# ucus_kontrol.net
KiCad netlist of a schematic drawn in Altium Designer
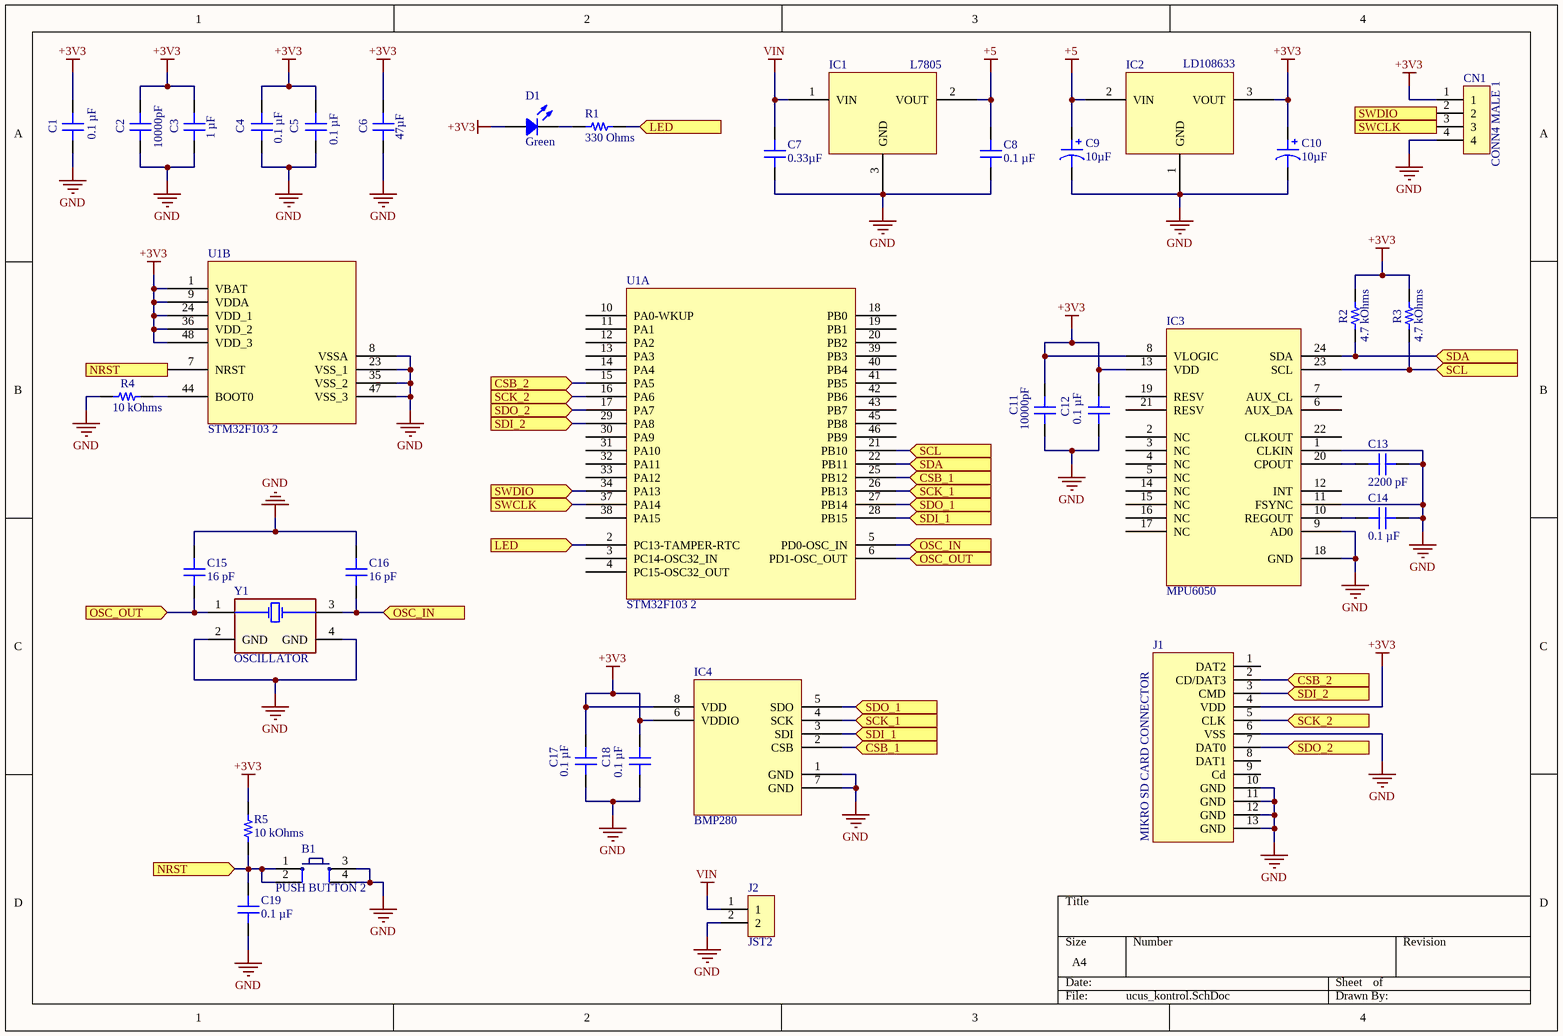
[diagram p0: ucus_kontrol.SchDoc]

(export (version "E")
  (design (tool "Eeschema 10.0.6"))
  (components
    (comp (ref "B1")
      (value "PUSH BUTTON 2")
      (footprint "PUSH BUTTON 2")
      (libsource (lib "UcusKontrol_Library") (part "PUSH BUTTON 2"))
    )
    (comp (ref "C1")
      (value "0.1 µF")
      (footprint "CAP 1206_3216 - 0.8MM")
      (description "CAP CER 0.1UF 50V X7R 1206")
      (fields
        (field (name "PART NUMBER") "1206B104M500CT")
        (field (name "MANUFACTURER") "Walsin Technology Corporation")
      )
      (libsource (lib "Celestial Altium Library - altium_library") (part "Capacitor"))
    )
    (comp (ref "C2")
      (value "10000pF")
      (footprint "CAP 1206_3216 - 1.0MM")
      (description "CAP CER 10000PF 50V X7R 1206")
      (fields (field (name "PART NUMBER") "12065C103K4T2A") (field (name "MANUFACTURER") "AVX Corporation"))
      (libsource (lib "Celestial Altium Library - altium_library") (part "Capacitor"))
    )
    (comp (ref "C3")
      (value "1 µF")
      (footprint "CAP 1206_3216 - 0.8MM")
      (description "CAP CER 1206 1UF 25V X7R")
      (fields (field (name "PART NUMBER") "C1206X105K3RAC3316") (field (name "MANUFACTURER") "KEMET"))
      (libsource (lib "Celestial Altium Library - altium_library") (part "Capacitor"))
    )
    (comp (ref "C4")
      (value "0.1 µF")
      (footprint "CAP 1206_3216 - 0.8MM")
      (description "CAP CER 0.1UF 50V X7R 1206")
      (fields
        (field (name "PART NUMBER") "1206B104M500CT")
        (field (name "MANUFACTURER") "Walsin Technology Corporation")
      )
      (libsource (lib "Celestial Altium Library - altium_library") (part "Capacitor"))
    )
    (comp (ref "C5")
      (value "0.1 µF")
      (footprint "CAP 1206_3216 - 0.8MM")
      (description "CAP CER 0.1UF 50V X7R 1206")
      (fields
        (field (name "PART NUMBER") "1206B104M500CT")
        (field (name "MANUFACTURER") "Walsin Technology Corporation")
      )
      (libsource (lib "Celestial Altium Library - altium_library") (part "Capacitor"))
    )
    (comp (ref "C6")
      (value "47µF")
      (footprint "CAP 1206_3216 - 1.8MM")
      (description "CAP CER 47UF 6.3V X5R 1206")
      (fields (field (name "PART NUMBER") "12066D476MAT2A") (field (name "MANUFACTURER") "AVX Corporation"))
      (libsource (lib "Celestial Altium Library - altium_library") (part "Capacitor"))
    )
    (comp (ref "C7")
      (value "0.33µF")
      (footprint "CAP 1206_3216 - 1.0MM")
      (description "CAP CER 0.33UF 50V Z5U 1206")
      (fields (field (name "PART NUMBER") "12065E334MAT2A") (field (name "MANUFACTURER") "AVX Corporation"))
      (libsource (lib "Celestial Altium Library - altium_library") (part "Capacitor"))
    )
    (comp (ref "C8")
      (value "0.1 µF")
      (footprint "CAP 1206_3216 - 0.8MM")
      (description "CAP CER 0.1UF 50V X7R 1206")
      (fields
        (field (name "PART NUMBER") "1206B104M500CT")
        (field (name "MANUFACTURER") "Walsin Technology Corporation")
      )
      (libsource (lib "Celestial Altium Library - altium_library") (part "Capacitor"))
    )
    (comp (ref "C9")
      (value "10µF")
      (footprint "CAP POL 1206_3216")
      (description "CAP TANT 10UF 20% 25V 1206")
      (fields (field (name "PART NUMBER") "F951E106MAAAQ2") (field (name "MANUFACTURER") "AVX Corporation"))
      (libsource (lib "Celestial Altium Library - altium_library") (part "Polarised Capacitor"))
    )
    (comp (ref "C10")
      (value "10µF")
      (footprint "CAP POL 1206_3216")
      (description "CAP TANT 10UF 20% 25V 1206")
      (fields (field (name "PART NUMBER") "F951E106MAAAQ2") (field (name "MANUFACTURER") "AVX Corporation"))
      (libsource (lib "Celestial Altium Library - altium_library") (part "Polarised Capacitor"))
    )
    (comp (ref "C11")
      (value "10000pF")
      (footprint "CAP 1206_3216 - 1.0MM")
      (description "CAP CER 10000PF 50V X7R 1206")
      (fields (field (name "PART NUMBER") "12065C103K4T2A") (field (name "MANUFACTURER") "AVX Corporation"))
      (libsource (lib "Celestial Altium Library - altium_library") (part "Capacitor"))
    )
    (comp (ref "C12")
      (value "0.1 µF")
      (footprint "CAP 1206_3216 - 0.8MM")
      (description "CAP CER 0.1UF 50V X7R 1206")
      (fields
        (field (name "PART NUMBER") "1206B104M500CT")
        (field (name "MANUFACTURER") "Walsin Technology Corporation")
      )
      (libsource (lib "Celestial Altium Library - altium_library") (part "Capacitor"))
    )
    (comp (ref "C13")
      (value "2200 pF")
      (footprint "CAP 1206_3216 - 0.8MM")
      (description "CAP CER 2200PF 50V C0G/NP0 1206")
      (fields
        (field (name "PART NUMBER") "CL31C222JBCNNNC")
        (field (name "MANUFACTURER") "Samsung Electro-Mechanics")
      )
      (libsource (lib "Celestial Altium Library - altium_library") (part "Capacitor"))
    )
    (comp (ref "C14")
      (value "0.1 µF")
      (footprint "CAP 1206_3216 - 0.8MM")
      (description "CAP CER 0.1UF 50V X7R 1206")
      (fields
        (field (name "PART NUMBER") "1206B104M500CT")
        (field (name "MANUFACTURER") "Walsin Technology Corporation")
      )
      (libsource (lib "Celestial Altium Library - altium_library") (part "Capacitor"))
    )
    (comp (ref "C15")
      (value "16 pF")
      (footprint "CAP 1206_3216 - 0.8MM")
      (description "CAP CER 16PF 50V NP0 1206")
      (fields (field (name "PART NUMBER") "C1206C160J5GAC7800") (field (name "MANUFACTURER") "KEMET"))
      (libsource (lib "Celestial Altium Library - altium_library") (part "Capacitor"))
    )
    (comp (ref "C16")
      (value "16 pF")
      (footprint "CAP 1206_3216 - 0.8MM")
      (description "CAP CER 16PF 50V NP0 1206")
      (fields (field (name "PART NUMBER") "C1206C160J5GAC7800") (field (name "MANUFACTURER") "KEMET"))
      (libsource (lib "Celestial Altium Library - altium_library") (part "Capacitor"))
    )
    (comp (ref "C17")
      (value "0.1 µF")
      (footprint "CAP 1206_3216 - 0.8MM")
      (description "CAP CER 0.1UF 50V X7R 1206")
      (fields
        (field (name "PART NUMBER") "1206B104M500CT")
        (field (name "MANUFACTURER") "Walsin Technology Corporation")
      )
      (libsource (lib "Celestial Altium Library - altium_library") (part "Capacitor"))
    )
    (comp (ref "C18")
      (value "0.1 µF")
      (footprint "CAP 1206_3216 - 0.8MM")
      (description "CAP CER 0.1UF 50V X7R 1206")
      (fields
        (field (name "PART NUMBER") "1206B104M500CT")
        (field (name "MANUFACTURER") "Walsin Technology Corporation")
      )
      (libsource (lib "Celestial Altium Library - altium_library") (part "Capacitor"))
    )
    (comp (ref "C19")
      (value "0.1 µF")
      (footprint "CAP 1206_3216 - 0.8MM")
      (description "CAP CER 0.1UF 50V X7R 1206")
      (fields
        (field (name "PART NUMBER") "1206B104M500CT")
        (field (name "MANUFACTURER") "Walsin Technology Corporation")
      )
      (libsource (lib "Celestial Altium Library - altium_library") (part "Capacitor"))
    )
    (comp (ref "CN1")
      (value "CONN4 MALE 1")
      (footprint "CONN4 MALE 1")
      (description "4 PIN 2.54MM")
      (libsource (lib "UcusKontrol_Library") (part "CONN4 MALE 1"))
    )
    (comp (ref "D1")
      (value "Green")
      (footprint "LED 0805_2012 GREEN")
      (description "LED GREEN 0805 SMD")
      (fields (field (name "PART NUMBER") "5975316507F") (field (name "MANUFACTURER") "Dialight"))
      (libsource (lib "Celestial Altium Library - altium_library") (part "LED"))
    )
    (comp (ref "IC1")
      (value "L7805")
      (footprint "DPAK")
      (description "IC-7805 V.REG.+5V 1.5A DPAK TO252")
      (libsource (lib "UcusKontrol_Library") (part "L7805"))
    )
    (comp (ref "IC2")
      (value "LD108633")
      (footprint "DPAK")
      (description "IC-1086 V.REG LDO 3.3V 1.5A TO-252 (DPAK)")
      (libsource (lib "UcusKontrol_Library") (part "LD108633"))
    )
    (comp (ref "IC3")
      (value "MPU6050")
      (footprint "QFN")
      (description "IC-6050 SENSOR MOTION QFN24")
      (libsource (lib "UcusKontrol_Library") (part "MPU6050"))
    )
    (comp (ref "IC4")
      (value "BMP280")
      (footprint "BMP280")
      (libsource (lib "UcusKontrol_Library") (part "BMP280"))
    )
    (comp (ref "J1")
      (value "MIKRO SD CARD CONNECTOR")
      (footprint "MICRO SD CARD CONNECTOR")
      (libsource (lib "UcusKontrol_Library") (part "MIKRO SD CARD CONNECTOR"))
    )
    (comp (ref "J2")
      (value "JST2")
      (footprint "JST2")
      (description "2 PIN 2.54MM")
      (libsource (lib "UcusKontrol_Library") (part "JST2"))
    )
    (comp (ref "R1")
      (value "330 Ohms")
      (footprint "RES 0805_2012")
      (description "RES SMD 330 OHM 1% 1/8W 0805")
      (fields (field (name "PART NUMBER") "AC0805FR-07330RL") (field (name "MANUFACTURER") "Yageo"))
      (libsource (lib "Celestial Altium Library - altium_library") (part "Resistor"))
    )
    (comp (ref "R2")
      (value "4.7 kOhms")
      (footprint "RES 1206_3216")
      (description "RES 4.7K OHM 0.1% 2/5W 1206")
      (fields (field (name "PART NUMBER") "TNPW12064K70BEEA") (field (name "MANUFACTURER") "Vishay Dale"))
      (libsource (lib "Celestial Altium Library - altium_library") (part "Resistor"))
    )
    (comp (ref "R3")
      (value "4.7 kOhms")
      (footprint "RES 1206_3216")
      (description "RES 4.7K OHM 0.1% 2/5W 1206")
      (fields (field (name "PART NUMBER") "TNPW12064K70BEEA") (field (name "MANUFACTURER") "Vishay Dale"))
      (libsource (lib "Celestial Altium Library - altium_library") (part "Resistor"))
    )
    (comp (ref "R4")
      (value "10 kOhms")
      (footprint "RES 1206_3216")
      (description "RES SMD 10K OHM 1% 1/4W 1206")
      (fields (field (name "PART NUMBER") "CRCW120610K0FKTA") (field (name "MANUFACTURER") "Vishay Dale"))
      (libsource (lib "Celestial Altium Library - altium_library") (part "Resistor"))
    )
    (comp (ref "R5")
      (value "10 kOhms")
      (footprint "RES 1206_3216")
      (description "RES SMD 10K OHM 1% 1/4W 1206")
      (fields (field (name "PART NUMBER") "CRCW120610K0FKTA") (field (name "MANUFACTURER") "Vishay Dale"))
      (libsource (lib "Celestial Altium Library - altium_library") (part "Resistor"))
    )
    (comp (ref "U1")
      (value "STM32F103 2")
      (footprint "LQFP48")
      (libsource (lib "UcusKontrol_Library") (part "STM32F103 2"))
    )
    (comp (ref "Y1")
      (value "OSCILLATOR")
      (footprint "OSCILLATOR")
      (description "8MHZ 12.5pF")
      (libsource (lib "UcusKontrol_Library") (part "OSCILLATOR"))
    )
  )
  (nets
    (net (code "1") (name "+3V3") (class "Default")
      (node (ref "C1") (pin "2") (pinfunction "2_2") (pintype "passive"))
      (node (ref "C10") (pin "1") (pinfunction "1_1") (pintype "passive"))
      (node (ref "C11") (pin "2") (pinfunction "2_2") (pintype "passive"))
      (node (ref "C12") (pin "1") (pinfunction "1_1") (pintype "passive"))
      (node (ref "C17") (pin "2") (pinfunction "2_2") (pintype "passive"))
      (node (ref "C18") (pin "2") (pinfunction "2_2") (pintype "passive"))
      (node (ref "C2") (pin "2") (pinfunction "2_2") (pintype "passive"))
      (node (ref "C3") (pin "2") (pinfunction "2_2") (pintype "passive"))
      (node (ref "C4") (pin "2") (pinfunction "2_2") (pintype "passive"))
      (node (ref "C5") (pin "2") (pinfunction "2_2") (pintype "passive"))
      (node (ref "C6") (pin "2") (pinfunction "2_2") (pintype "passive"))
      (node (ref "CN1") (pin "1") (pinfunction "1_1") (pintype "passive"))
      (node (ref "D1") (pin "1") (pinfunction "1_1") (pintype "passive"))
      (node (ref "IC2") (pin "3") (pinfunction "VOUT_3") (pintype "passive"))
      (node (ref "IC3") (pin "13") (pinfunction "VDD_13") (pintype "passive"))
      (node (ref "IC3") (pin "8") (pinfunction "VLOGIC_8") (pintype "passive"))
      (node (ref "IC4") (pin "6") (pinfunction "VDDIO_6") (pintype "passive"))
      (node (ref "IC4") (pin "8") (pinfunction "VDD_8") (pintype "passive"))
      (node (ref "J1") (pin "4") (pinfunction "VDD_4") (pintype "passive"))
      (node (ref "R2") (pin "2") (pinfunction "2_2") (pintype "passive"))
      (node (ref "R3") (pin "2") (pinfunction "2_2") (pintype "passive"))
      (node (ref "R5") (pin "2") (pinfunction "2_2") (pintype "passive"))
      (node (ref "U1") (pin "1") (pinfunction "VBAT_1") (pintype "passive"))
      (node (ref "U1") (pin "24") (pinfunction "VDD_1_24") (pintype "passive"))
      (node (ref "U1") (pin "36") (pinfunction "VDD_2_36") (pintype "passive"))
      (node (ref "U1") (pin "48") (pinfunction "VDD_3_48") (pintype "passive"))
      (node (ref "U1") (pin "9") (pinfunction "VDDA_9") (pintype "passive"))
    )
    (net (code "2") (name "+5") (class "Default")
      (node (ref "C8") (pin "2") (pinfunction "2_2") (pintype "passive"))
      (node (ref "C9") (pin "1") (pinfunction "1_1") (pintype "passive"))
      (node (ref "IC1") (pin "2") (pinfunction "VOUT_2") (pintype "passive"))
      (node (ref "IC2") (pin "2") (pinfunction "VIN_2") (pintype "passive"))
    )
    (net (code "3") (name "/CSB_1") (class "Default")
      (node (ref "IC4") (pin "2") (pinfunction "CSB_2") (pintype "passive"))
      (node (ref "U1") (pin "25") (pinfunction "PB12_25") (pintype "passive"))
    )
    (net (code "4") (name "/CSB_2") (class "Default")
      (node (ref "J1") (pin "2") (pinfunction "CD/DAT3_2") (pintype "passive"))
      (node (ref "U1") (pin "15") (pinfunction "PA5_15") (pintype "passive"))
    )
    (net (code "5") (name "/LED") (class "Default")
      (node (ref "R1") (pin "2") (pinfunction "2_2") (pintype "passive"))
      (node (ref "U1") (pin "2") (pinfunction "PC13-TAMPER-RTC_2") (pintype "passive"))
    )
    (net (code "6") (name "/NRST") (class "Default")
      (node (ref "B1") (pin "1") (pinfunction "1_1") (pintype "passive"))
      (node (ref "B1") (pin "2") (pinfunction "2_2") (pintype "passive"))
      (node (ref "C19") (pin "2") (pinfunction "2_2") (pintype "passive"))
      (node (ref "R5") (pin "1") (pinfunction "1_1") (pintype "passive"))
      (node (ref "U1") (pin "7") (pinfunction "NRST_7") (pintype "passive"))
    )
    (net (code "7") (name "/OSC_IN") (class "Default")
      (node (ref "C16") (pin "1") (pinfunction "1_1") (pintype "passive"))
      (node (ref "U1") (pin "5") (pinfunction "PD0-OSC_IN_5") (pintype "passive"))
      (node (ref "Y1") (pin "3") (pintype "passive"))
    )
    (net (code "8") (name "/OSC_OUT") (class "Default")
      (node (ref "C15") (pin "1") (pinfunction "1_1") (pintype "passive"))
      (node (ref "U1") (pin "6") (pinfunction "PD1-OSC_OUT_6") (pintype "passive"))
      (node (ref "Y1") (pin "1") (pintype "power_in"))
    )
    (net (code "9") (name "/SCK_1") (class "Default")
      (node (ref "IC4") (pin "4") (pinfunction "SCK_4") (pintype "passive"))
      (node (ref "U1") (pin "26") (pinfunction "PB13_26") (pintype "passive"))
    )
    (net (code "10") (name "/SCK_2") (class "Default")
      (node (ref "J1") (pin "5") (pinfunction "CLK_5") (pintype "passive"))
      (node (ref "U1") (pin "16") (pinfunction "PA6_16") (pintype "passive"))
    )
    (net (code "11") (name "/SCL") (class "Default")
      (node (ref "IC3") (pin "23") (pinfunction "SCL_23") (pintype "passive"))
      (node (ref "R3") (pin "1") (pinfunction "1_1") (pintype "passive"))
      (node (ref "U1") (pin "21") (pinfunction "PB10_21") (pintype "passive"))
    )
    (net (code "12") (name "/SDA") (class "Default")
      (node (ref "IC3") (pin "24") (pinfunction "SDA_24") (pintype "passive"))
      (node (ref "R2") (pin "1") (pinfunction "1_1") (pintype "passive"))
      (node (ref "U1") (pin "22") (pinfunction "PB11_22") (pintype "passive"))
    )
    (net (code "13") (name "/SDI_1") (class "Default")
      (node (ref "IC4") (pin "3") (pinfunction "SDI_3") (pintype "passive"))
      (node (ref "U1") (pin "28") (pinfunction "PB15_28") (pintype "passive"))
    )
    (net (code "14") (name "/SDI_2") (class "Default")
      (node (ref "J1") (pin "3") (pinfunction "CMD_3") (pintype "passive"))
      (node (ref "U1") (pin "29") (pinfunction "PA8_29") (pintype "passive"))
    )
    (net (code "15") (name "/SDO_1") (class "Default")
      (node (ref "IC4") (pin "5") (pinfunction "SDO_5") (pintype "passive"))
      (node (ref "U1") (pin "27") (pinfunction "PB14_27") (pintype "passive"))
    )
    (net (code "16") (name "/SDO_2") (class "Default")
      (node (ref "J1") (pin "7") (pinfunction "DAT0_7") (pintype "passive"))
      (node (ref "U1") (pin "17") (pinfunction "PA7_17") (pintype "passive"))
    )
    (net (code "17") (name "/SWCLK") (class "Default")
      (node (ref "CN1") (pin "3") (pinfunction "3_3") (pintype "passive"))
      (node (ref "U1") (pin "37") (pinfunction "PA14_37") (pintype "passive"))
    )
    (net (code "18") (name "/SWDIO") (class "Default")
      (node (ref "CN1") (pin "2") (pinfunction "2_2") (pintype "passive"))
      (node (ref "U1") (pin "34") (pinfunction "PA13_34") (pintype "passive"))
    )
    (net (code "19") (name "GND") (class "Default")
      (node (ref "B1") (pin "3") (pinfunction "3_3") (pintype "passive"))
      (node (ref "B1") (pin "4") (pinfunction "4_4") (pintype "passive"))
      (node (ref "C1") (pin "1") (pinfunction "1_1") (pintype "passive"))
      (node (ref "C10") (pin "2") (pinfunction "2_2") (pintype "passive"))
      (node (ref "C11") (pin "1") (pinfunction "1_1") (pintype "passive"))
      (node (ref "C12") (pin "2") (pinfunction "2_2") (pintype "passive"))
      (node (ref "C13") (pin "2") (pinfunction "2_2") (pintype "passive"))
      (node (ref "C14") (pin "2") (pinfunction "2_2") (pintype "passive"))
      (node (ref "C15") (pin "2") (pinfunction "2_2") (pintype "passive"))
      (node (ref "C16") (pin "2") (pinfunction "2_2") (pintype "passive"))
      (node (ref "C17") (pin "1") (pinfunction "1_1") (pintype "passive"))
      (node (ref "C18") (pin "1") (pinfunction "1_1") (pintype "passive"))
      (node (ref "C19") (pin "1") (pinfunction "1_1") (pintype "passive"))
      (node (ref "C2") (pin "1") (pinfunction "1_1") (pintype "passive"))
      (node (ref "C3") (pin "1") (pinfunction "1_1") (pintype "passive"))
      (node (ref "C4") (pin "1") (pinfunction "1_1") (pintype "passive"))
      (node (ref "C5") (pin "1") (pinfunction "1_1") (pintype "passive"))
      (node (ref "C6") (pin "1") (pinfunction "1_1") (pintype "passive"))
      (node (ref "C7") (pin "1") (pinfunction "1_1") (pintype "passive"))
      (node (ref "C8") (pin "1") (pinfunction "1_1") (pintype "passive"))
      (node (ref "C9") (pin "2") (pinfunction "2_2") (pintype "passive"))
      (node (ref "CN1") (pin "4") (pinfunction "4_4") (pintype "passive"))
      (node (ref "IC1") (pin "3") (pinfunction "GND_3") (pintype "passive"))
      (node (ref "IC2") (pin "1") (pinfunction "GND_1") (pintype "passive"))
      (node (ref "IC3") (pin "1") (pinfunction "CLKIN_1") (pintype "passive"))
      (node (ref "IC3") (pin "11") (pinfunction "FSYNC_11") (pintype "passive"))
      (node (ref "IC3") (pin "18") (pinfunction "GND_18") (pintype "passive"))
      (node (ref "IC3") (pin "9") (pinfunction "AD0_9") (pintype "passive"))
      (node (ref "IC4") (pin "1") (pinfunction "GND_1") (pintype "passive"))
      (node (ref "IC4") (pin "7") (pinfunction "GND_7") (pintype "passive"))
      (node (ref "J1") (pin "10") (pinfunction "GND_10") (pintype "passive"))
      (node (ref "J1") (pin "11") (pinfunction "GND_11") (pintype "passive"))
      (node (ref "J1") (pin "12") (pinfunction "GND_12") (pintype "passive"))
      (node (ref "J1") (pin "13") (pinfunction "GND_13") (pintype "passive"))
      (node (ref "J1") (pin "6") (pinfunction "VSS_6") (pintype "passive"))
      (node (ref "J2") (pin "2") (pinfunction "2_2") (pintype "passive"))
      (node (ref "R4") (pin "1") (pinfunction "1_1") (pintype "passive"))
      (node (ref "U1") (pin "23") (pinfunction "VSS_1_23") (pintype "passive"))
      (node (ref "U1") (pin "35") (pinfunction "VSS_2_35") (pintype "passive"))
      (node (ref "U1") (pin "47") (pinfunction "VSS_3_47") (pintype "passive"))
      (node (ref "U1") (pin "8") (pinfunction "VSSA_8") (pintype "passive"))
      (node (ref "Y1") (pin "2") (pinfunction "GND_2") (pintype "power_in"))
      (node (ref "Y1") (pin "4") (pinfunction "GND_4") (pintype "passive"))
    )
    (net (code "20") (name "Net-(D1-Pad2)") (class "Default")
      (node (ref "D1") (pin "2") (pinfunction "2_2") (pintype "passive"))
      (node (ref "R1") (pin "1") (pinfunction "1_1") (pintype "passive"))
    )
    (net (code "21") (name "Net-(IC3-CPOUT)") (class "Default")
      (node (ref "C13") (pin "1") (pinfunction "1_1") (pintype "passive"))
      (node (ref "IC3") (pin "20") (pinfunction "CPOUT_20") (pintype "passive"))
    )
    (net (code "22") (name "Net-(IC3-REGOUT)") (class "Default")
      (node (ref "C14") (pin "1") (pinfunction "1_1") (pintype "passive"))
      (node (ref "IC3") (pin "10") (pinfunction "REGOUT_10") (pintype "passive"))
    )
    (net (code "23") (name "Net-(U1B-BOOT0)") (class "Default")
      (node (ref "R4") (pin "2") (pinfunction "2_2") (pintype "passive"))
      (node (ref "U1") (pin "44") (pinfunction "BOOT0_44") (pintype "passive"))
    )
    (net (code "24") (name "VIN") (class "Default")
      (node (ref "C7") (pin "2") (pinfunction "2_2") (pintype "passive"))
      (node (ref "IC1") (pin "1") (pinfunction "VIN_1") (pintype "passive"))
      (node (ref "J2") (pin "1") (pinfunction "1_1") (pintype "passive"))
    )
    (net (code "25") (name "unconnected-(IC3-AUX_CL-Pad7)") (class "Default")
      (node (ref "IC3") (pin "7") (pinfunction "AUX_CL_7") (pintype "passive"))
    )
    (net (code "26") (name "unconnected-(IC3-AUX_DA-Pad6)") (class "Default")
      (node (ref "IC3") (pin "6") (pinfunction "AUX_DA_6") (pintype "passive"))
    )
    (net (code "27") (name "unconnected-(IC3-CLKOUT-Pad22)") (class "Default")
      (node (ref "IC3") (pin "22") (pinfunction "CLKOUT_22") (pintype "passive"))
    )
    (net (code "28") (name "unconnected-(IC3-INT-Pad12)") (class "Default")
      (node (ref "IC3") (pin "12") (pinfunction "INT_12") (pintype "passive"))
    )
    (net (code "29") (name "unconnected-(IC3-NC-Pad2)") (class "Default")
      (node (ref "IC3") (pin "2") (pinfunction "NC_2") (pintype "passive"))
    )
    (net (code "30") (name "unconnected-(IC3-NC-Pad3)") (class "Default")
      (node (ref "IC3") (pin "3") (pinfunction "NC_3") (pintype "passive"))
    )
    (net (code "31") (name "unconnected-(IC3-NC-Pad4)") (class "Default")
      (node (ref "IC3") (pin "4") (pinfunction "NC_4") (pintype "passive"))
    )
    (net (code "32") (name "unconnected-(IC3-NC-Pad5)") (class "Default")
      (node (ref "IC3") (pin "5") (pinfunction "NC_5") (pintype "passive"))
    )
    (net (code "33") (name "unconnected-(IC3-NC-Pad14)") (class "Default")
      (node (ref "IC3") (pin "14") (pinfunction "NC_14") (pintype "passive"))
    )
    (net (code "34") (name "unconnected-(IC3-NC-Pad15)") (class "Default")
      (node (ref "IC3") (pin "15") (pinfunction "NC_15") (pintype "passive"))
    )
    (net (code "35") (name "unconnected-(IC3-NC-Pad16)") (class "Default")
      (node (ref "IC3") (pin "16") (pinfunction "NC_16") (pintype "passive"))
    )
    (net (code "36") (name "unconnected-(IC3-NC-Pad17)") (class "Default")
      (node (ref "IC3") (pin "17") (pinfunction "NC_17") (pintype "passive"))
    )
    (net (code "37") (name "unconnected-(IC3-RESV-Pad19)") (class "Default")
      (node (ref "IC3") (pin "19") (pinfunction "RESV_19") (pintype "passive"))
    )
    (net (code "38") (name "unconnected-(IC3-RESV-Pad21)") (class "Default")
      (node (ref "IC3") (pin "21") (pinfunction "RESV_21") (pintype "passive"))
    )
    (net (code "39") (name "unconnected-(J1-Cd-Pad9)") (class "Default")
      (node (ref "J1") (pin "9") (pinfunction "Cd_9") (pintype "passive"))
    )
    (net (code "40") (name "unconnected-(J1-DAT1-Pad8)") (class "Default")
      (node (ref "J1") (pin "8") (pinfunction "DAT1_8") (pintype "passive"))
    )
    (net (code "41") (name "unconnected-(J1-DAT2-Pad1)") (class "Default")
      (node (ref "J1") (pin "1") (pinfunction "DAT2_1") (pintype "passive"))
    )
    (net (code "42") (name "unconnected-(U1A-PA0-WKUP-Pad10)") (class "Default")
      (node (ref "U1") (pin "10") (pinfunction "PA0-WKUP_10") (pintype "passive"))
    )
    (net (code "43") (name "unconnected-(U1A-PA1-Pad11)") (class "Default")
      (node (ref "U1") (pin "11") (pinfunction "PA1_11") (pintype "passive"))
    )
    (net (code "44") (name "unconnected-(U1A-PA2-Pad12)") (class "Default")
      (node (ref "U1") (pin "12") (pinfunction "PA2_12") (pintype "passive"))
    )
    (net (code "45") (name "unconnected-(U1A-PA3-Pad13)") (class "Default")
      (node (ref "U1") (pin "13") (pinfunction "PA3_13") (pintype "passive"))
    )
    (net (code "46") (name "unconnected-(U1A-PA4-Pad14)") (class "Default")
      (node (ref "U1") (pin "14") (pinfunction "PA4_14") (pintype "passive"))
    )
    (net (code "47") (name "unconnected-(U1A-PA9-Pad30)") (class "Default")
      (node (ref "U1") (pin "30") (pinfunction "PA9_30") (pintype "passive"))
    )
    (net (code "48") (name "unconnected-(U1A-PA10-Pad31)") (class "Default")
      (node (ref "U1") (pin "31") (pinfunction "PA10_31") (pintype "passive"))
    )
    (net (code "49") (name "unconnected-(U1A-PA11-Pad32)") (class "Default")
      (node (ref "U1") (pin "32") (pinfunction "PA11_32") (pintype "passive"))
    )
    (net (code "50") (name "unconnected-(U1A-PA12-Pad33)") (class "Default")
      (node (ref "U1") (pin "33") (pinfunction "PA12_33") (pintype "passive"))
    )
    (net (code "51") (name "unconnected-(U1A-PA15-Pad38)") (class "Default")
      (node (ref "U1") (pin "38") (pinfunction "PA15_38") (pintype "passive"))
    )
    (net (code "52") (name "unconnected-(U1A-PB0-Pad18)") (class "Default")
      (node (ref "U1") (pin "18") (pinfunction "PB0_18") (pintype "passive"))
    )
    (net (code "53") (name "unconnected-(U1A-PB1-Pad19)") (class "Default")
      (node (ref "U1") (pin "19") (pinfunction "PB1_19") (pintype "passive"))
    )
    (net (code "54") (name "unconnected-(U1A-PB2-Pad20)") (class "Default")
      (node (ref "U1") (pin "20") (pinfunction "PB2_20") (pintype "passive"))
    )
    (net (code "55") (name "unconnected-(U1A-PB3-Pad39)") (class "Default")
      (node (ref "U1") (pin "39") (pinfunction "PB3_39") (pintype "passive"))
    )
    (net (code "56") (name "unconnected-(U1A-PB4-Pad40)") (class "Default")
      (node (ref "U1") (pin "40") (pinfunction "PB4_40") (pintype "passive"))
    )
    (net (code "57") (name "unconnected-(U1A-PB5-Pad41)") (class "Default")
      (node (ref "U1") (pin "41") (pinfunction "PB5_41") (pintype "passive"))
    )
    (net (code "58") (name "unconnected-(U1A-PB6-Pad42)") (class "Default")
      (node (ref "U1") (pin "42") (pinfunction "PB6_42") (pintype "passive"))
    )
    (net (code "59") (name "unconnected-(U1A-PB7-Pad43)") (class "Default")
      (node (ref "U1") (pin "43") (pinfunction "PB7_43") (pintype "passive"))
    )
    (net (code "60") (name "unconnected-(U1A-PB8-Pad45)") (class "Default")
      (node (ref "U1") (pin "45") (pinfunction "PB8_45") (pintype "passive"))
    )
    (net (code "61") (name "unconnected-(U1A-PB9-Pad46)") (class "Default")
      (node (ref "U1") (pin "46") (pinfunction "PB9_46") (pintype "passive"))
    )
    (net (code "62") (name "unconnected-(U1A-PC14-OSC32_IN-Pad3)") (class "Default")
      (node (ref "U1") (pin "3") (pinfunction "PC14-OSC32_IN_3") (pintype "passive"))
    )
    (net (code "63") (name "unconnected-(U1A-PC15-OSC32_OUT-Pad4)") (class "Default")
      (node (ref "U1") (pin "4") (pinfunction "PC15-OSC32_OUT_4") (pintype "passive"))
    )
  )
)
